# ADC_Breakout.net
KiCad netlist of a schematic drawn in EAGLE
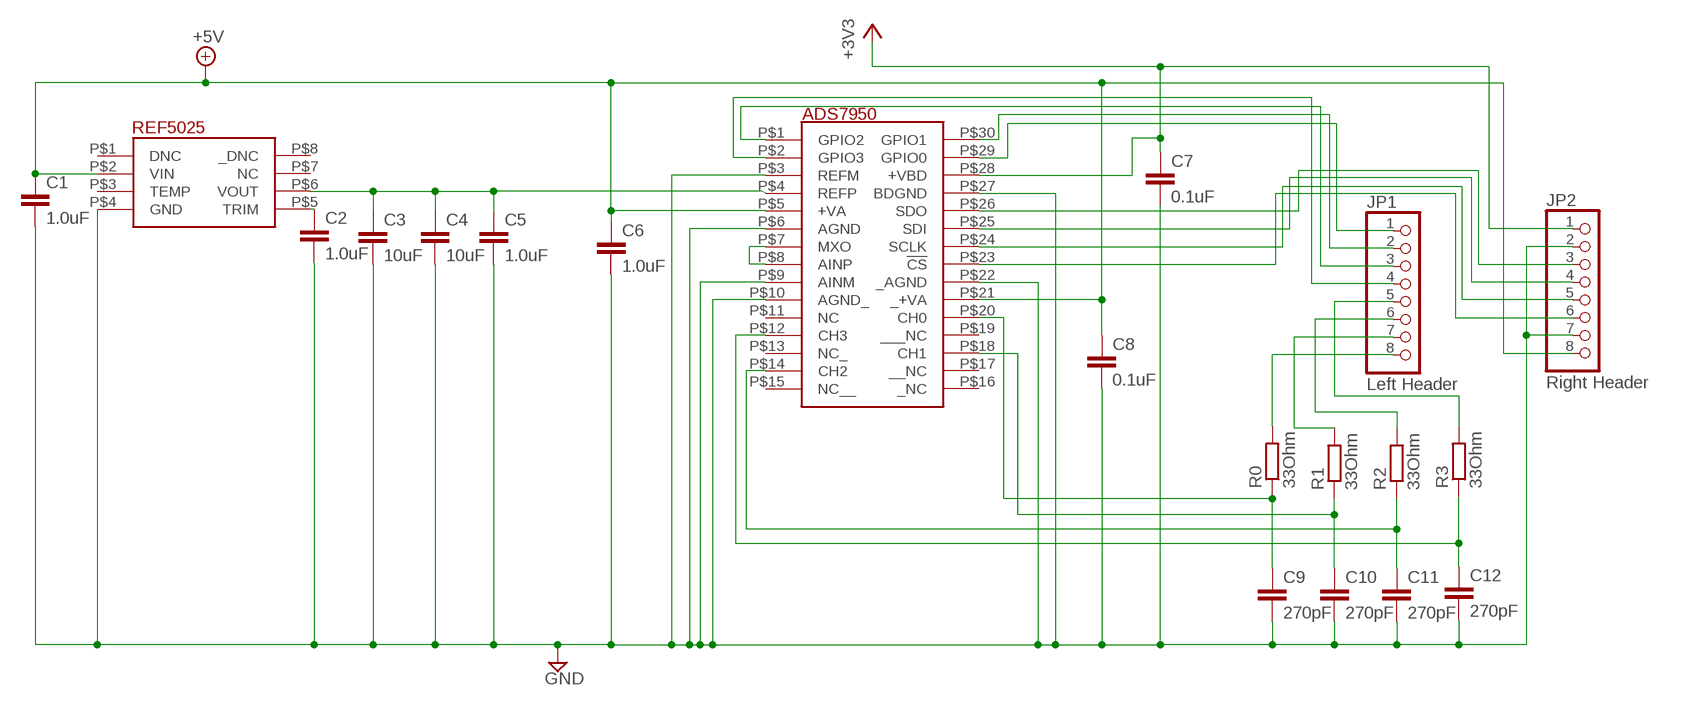
[diagram p0: schematic, sheet 1]

(export (version "E")
  (design (tool "Eeschema 10.0.6"))
  (components
    (comp (ref "ADS7950")
      (value "ADS7950")
      (footprint "eagle-import:TSSOP-30")
      (libsource (lib "eagle-import") (part "ADS7950"))
    )
    (comp (ref "C1")
      (value "1.0uF")
      (footprint "eagle-import:C0603")
      (libsource (lib "eagle-import") (part "C-EUC0603"))
    )
    (comp (ref "C2")
      (value "1.0uF")
      (footprint "eagle-import:C0603")
      (libsource (lib "eagle-import") (part "C-EUC0603"))
    )
    (comp (ref "C3")
      (value "10uF")
      (footprint "eagle-import:C0805")
      (libsource (lib "eagle-import") (part "C-EUC0805"))
    )
    (comp (ref "C4")
      (value "10uF")
      (footprint "eagle-import:C0805")
      (libsource (lib "eagle-import") (part "C-EUC0805"))
    )
    (comp (ref "C5")
      (value "1.0uF")
      (footprint "eagle-import:C0603")
      (libsource (lib "eagle-import") (part "C-EUC0603"))
    )
    (comp (ref "C6")
      (value "1.0uF")
      (footprint "eagle-import:C0603")
      (libsource (lib "eagle-import") (part "C-EUC0603"))
    )
    (comp (ref "C7")
      (value "0.1uF")
      (footprint "eagle-import:C0603")
      (libsource (lib "eagle-import") (part "C-EUC0603"))
    )
    (comp (ref "C8")
      (value "0.1uF")
      (footprint "eagle-import:C0603")
      (libsource (lib "eagle-import") (part "C-EUC0603"))
    )
    (comp (ref "C9")
      (value "270pF")
      (footprint "eagle-import:C0603")
      (libsource (lib "eagle-import") (part "C-EUC0603"))
    )
    (comp (ref "C10")
      (value "270pF")
      (footprint "eagle-import:C0603")
      (libsource (lib "eagle-import") (part "C-EUC0603"))
    )
    (comp (ref "C11")
      (value "270pF")
      (footprint "eagle-import:C0603")
      (libsource (lib "eagle-import") (part "C-EUC0603"))
    )
    (comp (ref "C12")
      (value "270pF")
      (footprint "eagle-import:C0603")
      (libsource (lib "eagle-import") (part "C-EUC0603"))
    )
    (comp (ref "JP1")
      (value "Left Header")
      (footprint "eagle-import:1X08")
      (libsource (lib "eagle-import") (part "PINHD-1X8"))
    )
    (comp (ref "JP2")
      (value "Right Header")
      (footprint "eagle-import:1X08")
      (libsource (lib "eagle-import") (part "PINHD-1X8"))
    )
    (comp (ref "R0")
      (value "33Ohm")
      (footprint "eagle-import:R1206")
      (libsource (lib "eagle-import") (part "R-EU_R1206"))
    )
    (comp (ref "R1")
      (value "33Ohm")
      (footprint "eagle-import:R1206")
      (libsource (lib "eagle-import") (part "R-EU_R1206"))
    )
    (comp (ref "R2")
      (value "33Ohm")
      (footprint "eagle-import:R1206")
      (libsource (lib "eagle-import") (part "R-EU_R1206"))
    )
    (comp (ref "R3")
      (value "33Ohm")
      (footprint "eagle-import:R1206")
      (libsource (lib "eagle-import") (part "R-EU_R1206"))
    )
    (comp (ref "REF5025")
      (value "REF5025")
      (footprint "eagle-import:SOIC-8")
      (libsource (lib "eagle-import") (part "REF5025"))
    )
  )
  (nets
    (net (code "1") (name "+3V3") (class "Default")
      (node (ref "ADS7950") (pin "P$28") (pinfunction "+VBD_P$28") (pintype "power_in"))
      (node (ref "C7") (pin "1") (pinfunction "1_1") (pintype "passive"))
      (node (ref "JP2") (pin "1") (pinfunction "1_1") (pintype "passive"))
    )
    (net (code "2") (name "+5V") (class "Default")
      (node (ref "ADS7950") (pin "P$21") (pinfunction "_+VA_P$21") (pintype "power_in"))
      (node (ref "ADS7950") (pin "P$5") (pinfunction "+VA_P$5") (pintype "power_in"))
      (node (ref "C1") (pin "1") (pinfunction "1_1") (pintype "passive"))
      (node (ref "C6") (pin "1") (pinfunction "1_1") (pintype "passive"))
      (node (ref "C8") (pin "1") (pinfunction "1_1") (pintype "passive"))
      (node (ref "JP2") (pin "8") (pinfunction "8_8") (pintype "passive"))
      (node (ref "REF5025") (pin "P$2") (pinfunction "VIN_P$2") (pintype "power_in"))
    )
    (net (code "3") (name "GND") (class "Default")
      (node (ref "ADS7950") (pin "P$10") (pinfunction "AGND__P$10") (pintype "power_in"))
      (node (ref "ADS7950") (pin "P$22") (pinfunction "_AGND_P$22") (pintype "power_in"))
      (node (ref "ADS7950") (pin "P$27") (pinfunction "BDGND_P$27") (pintype "power_in"))
      (node (ref "ADS7950") (pin "P$3") (pinfunction "REFM_P$3") (pintype "power_in"))
      (node (ref "ADS7950") (pin "P$6") (pinfunction "AGND_P$6") (pintype "power_in"))
      (node (ref "ADS7950") (pin "P$9") (pinfunction "AINM_P$9") (pintype "power_in"))
      (node (ref "C1") (pin "2") (pinfunction "2_2") (pintype "passive"))
      (node (ref "C10") (pin "2") (pinfunction "2_2") (pintype "passive"))
      (node (ref "C11") (pin "2") (pinfunction "2_2") (pintype "passive"))
      (node (ref "C12") (pin "2") (pinfunction "2_2") (pintype "passive"))
      (node (ref "C2") (pin "2") (pinfunction "2_2") (pintype "passive"))
      (node (ref "C3") (pin "2") (pinfunction "2_2") (pintype "passive"))
      (node (ref "C4") (pin "2") (pinfunction "2_2") (pintype "passive"))
      (node (ref "C5") (pin "2") (pinfunction "2_2") (pintype "passive"))
      (node (ref "C6") (pin "2") (pinfunction "2_2") (pintype "passive"))
      (node (ref "C7") (pin "2") (pinfunction "2_2") (pintype "passive"))
      (node (ref "C8") (pin "2") (pinfunction "2_2") (pintype "passive"))
      (node (ref "C9") (pin "2") (pinfunction "2_2") (pintype "passive"))
      (node (ref "JP2") (pin "2") (pinfunction "2_2") (pintype "passive"))
      (node (ref "JP2") (pin "7") (pinfunction "7_7") (pintype "passive"))
      (node (ref "REF5025") (pin "P$4") (pinfunction "GND_P$4") (pintype "power_in"))
    )
    (net (code "4") (name "Net-(ADS7950-AINP)") (class "Default")
      (node (ref "ADS7950") (pin "P$7") (pinfunction "MXO_P$7") (pintype "output"))
      (node (ref "ADS7950") (pin "P$8") (pinfunction "AINP_P$8") (pintype "input"))
    )
    (net (code "5") (name "Net-(ADS7950-CH0)") (class "Default")
      (node (ref "ADS7950") (pin "P$20") (pinfunction "CH0_P$20") (pintype "input"))
      (node (ref "C9") (pin "1") (pinfunction "1_1") (pintype "passive"))
      (node (ref "R0") (pin "1") (pinfunction "1_1") (pintype "passive"))
    )
    (net (code "6") (name "Net-(ADS7950-CH1)") (class "Default")
      (node (ref "ADS7950") (pin "P$18") (pinfunction "CH1_P$18") (pintype "input"))
      (node (ref "C10") (pin "1") (pinfunction "1_1") (pintype "passive"))
      (node (ref "R1") (pin "1") (pinfunction "1_1") (pintype "passive"))
    )
    (net (code "7") (name "Net-(ADS7950-CH2)") (class "Default")
      (node (ref "ADS7950") (pin "P$14") (pinfunction "CH2_P$14") (pintype "input"))
      (node (ref "C11") (pin "1") (pinfunction "1_1") (pintype "passive"))
      (node (ref "R2") (pin "1") (pinfunction "1_1") (pintype "passive"))
    )
    (net (code "8") (name "Net-(ADS7950-CH3)") (class "Default")
      (node (ref "ADS7950") (pin "P$12") (pinfunction "CH3_P$12") (pintype "input"))
      (node (ref "C12") (pin "1") (pinfunction "1_1") (pintype "passive"))
      (node (ref "R3") (pin "1") (pinfunction "1_1") (pintype "passive"))
    )
    (net (code "9") (name "Net-(ADS7950-GPIO0)") (class "Default")
      (node (ref "ADS7950") (pin "P$29") (pinfunction "GPIO0_P$29") (pintype "bidirectional"))
      (node (ref "JP1") (pin "1") (pinfunction "1_1") (pintype "passive"))
    )
    (net (code "10") (name "Net-(ADS7950-GPIO1)") (class "Default")
      (node (ref "ADS7950") (pin "P$30") (pinfunction "GPIO1_P$30") (pintype "bidirectional"))
      (node (ref "JP1") (pin "2") (pinfunction "2_2") (pintype "passive"))
    )
    (net (code "11") (name "Net-(ADS7950-GPIO2)") (class "Default")
      (node (ref "ADS7950") (pin "P$1") (pinfunction "GPIO2_P$1") (pintype "bidirectional"))
      (node (ref "JP1") (pin "3") (pinfunction "3_3") (pintype "passive"))
    )
    (net (code "12") (name "Net-(ADS7950-GPIO3)") (class "Default")
      (node (ref "ADS7950") (pin "P$2") (pinfunction "GPIO3_P$2") (pintype "bidirectional"))
      (node (ref "JP1") (pin "4") (pinfunction "4_4") (pintype "passive"))
    )
    (net (code "13") (name "Net-(ADS7950-REFP)") (class "Default")
      (node (ref "ADS7950") (pin "P$4") (pinfunction "REFP_P$4") (pintype "power_in"))
      (node (ref "C3") (pin "1") (pinfunction "1_1") (pintype "passive"))
      (node (ref "C4") (pin "1") (pinfunction "1_1") (pintype "passive"))
      (node (ref "C5") (pin "1") (pinfunction "1_1") (pintype "passive"))
      (node (ref "REF5025") (pin "P$6") (pinfunction "VOUT_P$6") (pintype "power_in"))
    )
    (net (code "14") (name "Net-(ADS7950-SCLK)") (class "Default")
      (node (ref "ADS7950") (pin "P$24") (pinfunction "SCLK_P$24") (pintype "input"))
      (node (ref "JP2") (pin "5") (pinfunction "5_5") (pintype "passive"))
    )
    (net (code "15") (name "Net-(ADS7950-SDI)") (class "Default")
      (node (ref "ADS7950") (pin "P$25") (pinfunction "SDI_P$25") (pintype "input"))
      (node (ref "JP2") (pin "4") (pinfunction "4_4") (pintype "passive"))
    )
    (net (code "16") (name "Net-(ADS7950-SDO)") (class "Default")
      (node (ref "ADS7950") (pin "P$26") (pinfunction "SDO_P$26") (pintype "output"))
      (node (ref "JP2") (pin "3") (pinfunction "3_3") (pintype "passive"))
    )
    (net (code "17") (name "Net-(ADS7950-~{CS})") (class "Default")
      (node (ref "ADS7950") (pin "P$23") (pinfunction "~{CS}_P$23") (pintype "input"))
      (node (ref "JP2") (pin "6") (pinfunction "6_6") (pintype "passive"))
    )
    (net (code "18") (name "Net-(JP1-Pad5)") (class "Default")
      (node (ref "JP1") (pin "5") (pinfunction "5_5") (pintype "passive"))
      (node (ref "R3") (pin "2") (pinfunction "2_2") (pintype "passive"))
    )
    (net (code "19") (name "Net-(JP1-Pad6)") (class "Default")
      (node (ref "JP1") (pin "6") (pinfunction "6_6") (pintype "passive"))
      (node (ref "R2") (pin "2") (pinfunction "2_2") (pintype "passive"))
    )
    (net (code "20") (name "Net-(JP1-Pad7)") (class "Default")
      (node (ref "JP1") (pin "7") (pinfunction "7_7") (pintype "passive"))
      (node (ref "R1") (pin "2") (pinfunction "2_2") (pintype "passive"))
    )
    (net (code "21") (name "Net-(JP1-Pad8)") (class "Default")
      (node (ref "JP1") (pin "8") (pinfunction "8_8") (pintype "passive"))
      (node (ref "R0") (pin "2") (pinfunction "2_2") (pintype "passive"))
    )
    (net (code "22") (name "Net-(REF5025-TRIM)") (class "Default")
      (node (ref "C2") (pin "1") (pinfunction "1_1") (pintype "passive"))
      (node (ref "REF5025") (pin "P$5") (pinfunction "TRIM_P$5") (pintype "bidirectional"))
    )
    (net (code "23") (name "unconnected-(ADS7950-NC-PadP$11)") (class "Default")
      (node (ref "ADS7950") (pin "P$11") (pinfunction "NC_P$11") (pintype "no_connect"))
    )
    (net (code "24") (name "unconnected-(ADS7950-NC_-PadP$13)") (class "Default")
      (node (ref "ADS7950") (pin "P$13") (pinfunction "NC__P$13") (pintype "no_connect"))
    )
    (net (code "25") (name "unconnected-(ADS7950-NC__-PadP$15)") (class "Default")
      (node (ref "ADS7950") (pin "P$15") (pinfunction "NC___P$15") (pintype "no_connect"))
    )
    (net (code "26") (name "unconnected-(ADS7950-_NC-PadP$16)") (class "Default")
      (node (ref "ADS7950") (pin "P$16") (pinfunction "_NC_P$16") (pintype "no_connect"))
    )
    (net (code "27") (name "unconnected-(ADS7950-__NC-PadP$17)") (class "Default")
      (node (ref "ADS7950") (pin "P$17") (pinfunction "__NC_P$17") (pintype "no_connect"))
    )
    (net (code "28") (name "unconnected-(ADS7950-___NC-PadP$19)") (class "Default")
      (node (ref "ADS7950") (pin "P$19") (pinfunction "___NC_P$19") (pintype "no_connect"))
    )
    (net (code "29") (name "unconnected-(REF5025-DNC-PadP$1)") (class "Default")
      (node (ref "REF5025") (pin "P$1") (pinfunction "DNC_P$1") (pintype "no_connect"))
    )
    (net (code "30") (name "unconnected-(REF5025-NC-PadP$7)") (class "Default")
      (node (ref "REF5025") (pin "P$7") (pinfunction "NC_P$7") (pintype "no_connect"))
    )
    (net (code "31") (name "unconnected-(REF5025-TEMP-PadP$3)") (class "Default")
      (node (ref "REF5025") (pin "P$3") (pinfunction "TEMP_P$3") (pintype "output"))
    )
    (net (code "32") (name "unconnected-(REF5025-_DNC-PadP$8)") (class "Default")
      (node (ref "REF5025") (pin "P$8") (pinfunction "_DNC_P$8") (pintype "no_connect"))
    )
  )
)
